# Control.net
KiCad netlist of a schematic drawn in Altium Designer
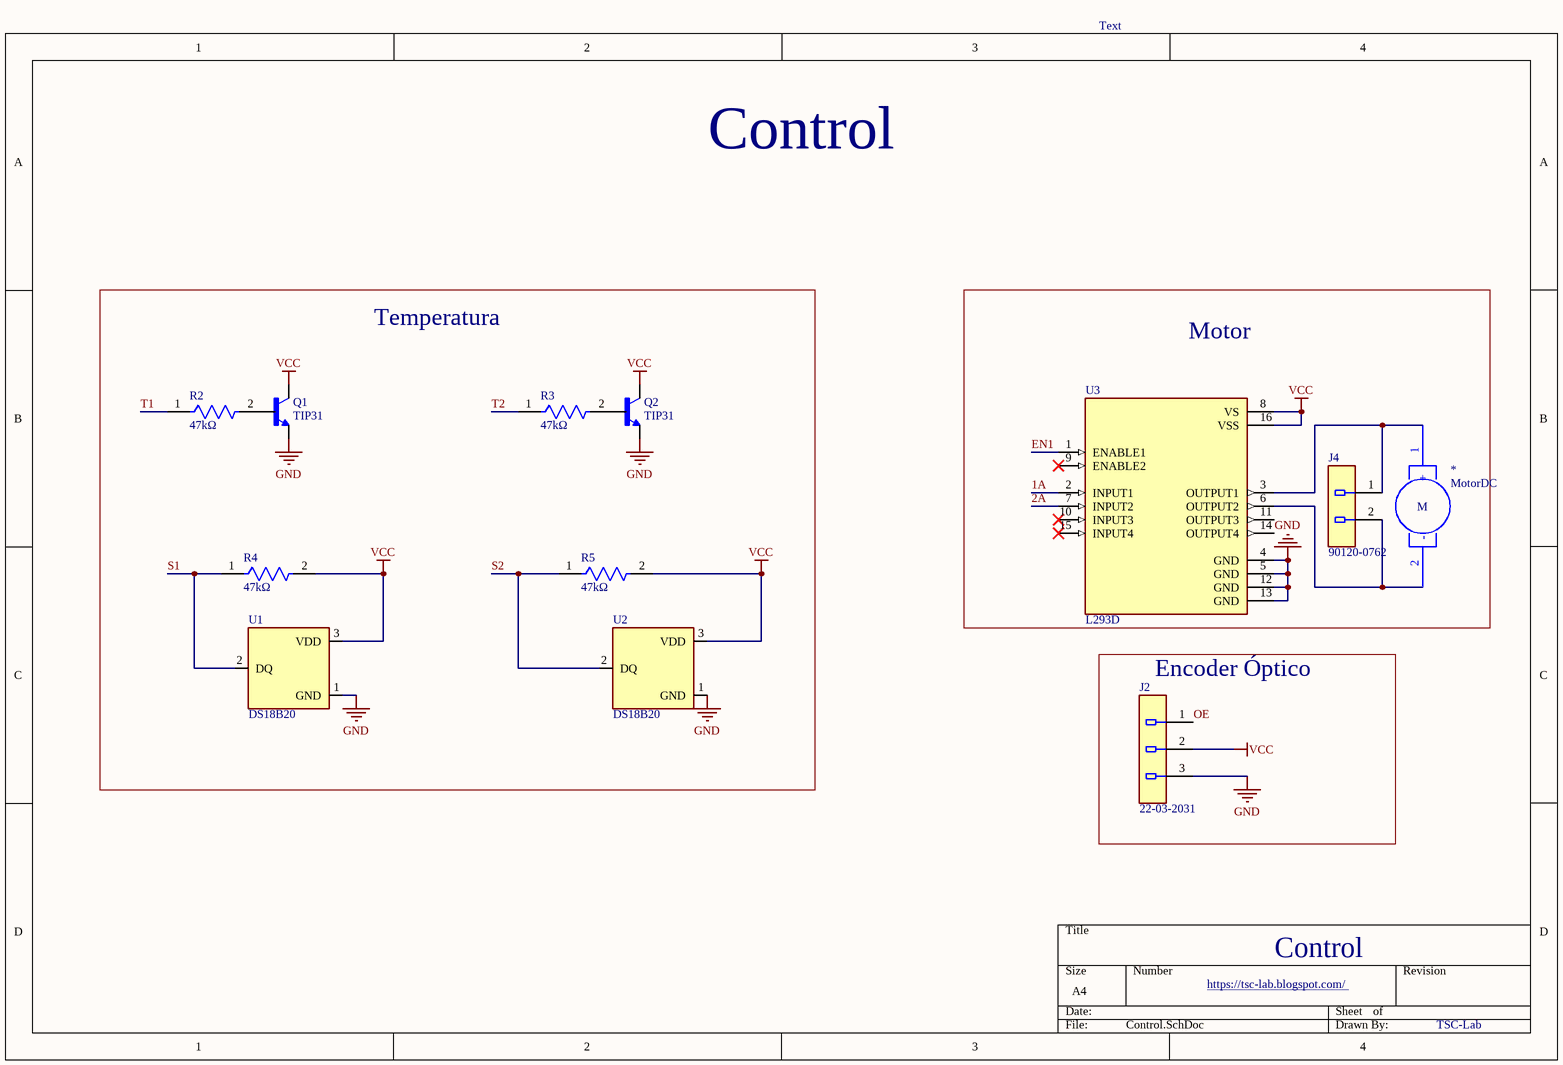
[diagram p0: Control.SchDoc]

(export (version "E")
  (design (tool "Eeschema 10.0.6"))
  (components
    (comp (ref "*")
      (value "MotorDC")
      (footprint "PCBComponent_1")
      (libsource (lib "SnapEDA_Library") (part "MotorDC"))
    )
    (comp (ref "J2")
      (value "Conn_Molex_22-03-2031_eec")
      (footprint "Molex_SD-4030-0001_0")
      (description "CONN HEADER 3POS .100 VERT TIN")
      (fields
        (field (name "PART NUMBER") "22-03-2031")
        (field (name "VOLTAGE") "150V")
        (field (name "MANUFACTURER") "Molex")
      )
      (libsource (lib "SnapEDA_Library") (part "Conn_Molex_22-03-2031_eec"))
    )
    (comp (ref "J4")
      (value "Conn_Molex_90120-0762_eec")
      (footprint "Molex_90120-0762_0")
      (description "CONN HEADER 2POS .100\" STR GOLD")
      (fields
        (field (name "MANUFACTURER") "Molex")
        (field (name "MOUSER PART NUMBER") "538-90120-0762")
        (field (name "PART NUMBER") "90120-0762")
      )
      (libsource (lib "SnapEDA_Library") (part "Conn_Molex_90120-0762_eec"))
    )
    (comp (ref "Q1")
      (value "TIP31")
      (footprint "TO254P1060X482X2222-3")
      (description "Bipolar (BJT) Transistor NPN 40V 3A 3MHz 2W Through Hole TO-220AB")
      (fields (field (name "MF") "{'manufacturer': u'ON Semiconductor'}"))
      (libsource (lib "SnapEDA_Library") (part "TIP31"))
    )
    (comp (ref "Q2")
      (value "TIP31")
      (footprint "TO254P1060X482X2222-3")
      (description "Bipolar (BJT) Transistor NPN 40V 3A 3MHz 2W Through Hole TO-220AB")
      (fields (field (name "MF") "{'manufacturer': u'ON Semiconductor'}"))
      (libsource (lib "SnapEDA_Library") (part "TIP31"))
    )
    (comp (ref "R2")
      (value "Res_Vishay_SFR2500002200FR500_eec")
      (footprint "Vishay_SFR2500002200FR500_0")
      (description "RES 220 OHM 0.4W 1% AXIAL")
      (fields
        (field (name "PART NUMBER") "SFR2500002200FR500")
        (field (name "VOLTAGE") "250 V")
        (field (name "RESISTANCE") "47kΩ")
      )
      (libsource (lib "SnapEDA_Library") (part "Res_Vishay_SFR2500002200FR500_eec"))
    )
    (comp (ref "R3")
      (value "Res_Vishay_SFR2500002200FR500_eec")
      (footprint "Vishay_SFR2500002200FR500_0")
      (description "RES 220 OHM 0.4W 1% AXIAL")
      (fields
        (field (name "PART NUMBER") "SFR2500002200FR500")
        (field (name "VOLTAGE") "250 V")
        (field (name "RESISTANCE") "47kΩ")
      )
      (libsource (lib "SnapEDA_Library") (part "Res_Vishay_SFR2500002200FR500_eec"))
    )
    (comp (ref "R4")
      (value "Res_Vishay_SFR2500002200FR500_eec")
      (footprint "Vishay_SFR2500002200FR500_0")
      (description "RES 220 OHM 0.4W 1% AXIAL")
      (fields
        (field (name "PART NUMBER") "SFR2500002200FR500")
        (field (name "VOLTAGE") "250 V")
        (field (name "RESISTANCE") "47kΩ")
      )
      (libsource (lib "SnapEDA_Library") (part "Res_Vishay_SFR2500002200FR500_eec"))
    )
    (comp (ref "R5")
      (value "Res_Vishay_SFR2500002200FR500_eec")
      (footprint "Vishay_SFR2500002200FR500_0")
      (description "RES 220 OHM 0.4W 1% AXIAL")
      (fields
        (field (name "PART NUMBER") "SFR2500002200FR500")
        (field (name "VOLTAGE") "250 V")
        (field (name "RESISTANCE") "47kΩ")
      )
      (libsource (lib "SnapEDA_Library") (part "Res_Vishay_SFR2500002200FR500_eec"))
    )
    (comp (ref "U1")
      (value "DS18B20")
      (footprint "TO-92-TO92127P495H2044-3")
      (description "digital thermometer -55C-125C TO92-3")
      (fields (field (name "MF") "{'manufacturer': u'Maxim Integrated'}"))
      (libsource (lib "SnapEDA_Library") (part "DS18B20"))
    )
    (comp (ref "U2")
      (value "DS18B20")
      (footprint "TO-92-TO92127P495H2044-3")
      (description "digital thermometer -55C-125C TO92-3")
      (fields (field (name "MF") "{'manufacturer': u'Maxim Integrated'}"))
      (libsource (lib "SnapEDA_Library") (part "DS18B20"))
    )
    (comp (ref "U3")
      (value "L293D")
      (footprint "DIP880W50P254L2000H510Q16")
      (description "4-Channel Motor Driver 24V 16-Pin Power PDIP Tube")
      (fields (field (name "MF") "{'manufacturer': u'STMicroelectronics'}"))
      (libsource (lib "SnapEDA_Library") (part "L293D"))
    )
  )
  (nets
    (net (code "1") (name "/1A") (class "Default")
      (node (ref "U3") (pin "2") (pinfunction "INPUT1_2") (pintype "input"))
    )
    (net (code "2") (name "/2A") (class "Default")
      (node (ref "U3") (pin "7") (pinfunction "INPUT2_7") (pintype "input"))
    )
    (net (code "3") (name "/EN1") (class "Default")
      (node (ref "U3") (pin "1") (pinfunction "ENABLE1_1") (pintype "input"))
    )
    (net (code "4") (name "/OE") (class "Default")
      (node (ref "J2") (pin "1") (pinfunction "1_1") (pintype "passive"))
    )
    (net (code "5") (name "/S1") (class "Default")
      (node (ref "R4") (pin "1") (pinfunction "1_1") (pintype "passive"))
      (node (ref "U1") (pin "2") (pinfunction "DQ_2") (pintype "bidirectional"))
    )
    (net (code "6") (name "/S2") (class "Default")
      (node (ref "R5") (pin "1") (pinfunction "1_1") (pintype "passive"))
      (node (ref "U2") (pin "2") (pinfunction "DQ_2") (pintype "bidirectional"))
    )
    (net (code "7") (name "/T1") (class "Default")
      (node (ref "R2") (pin "1") (pinfunction "1_1") (pintype "passive"))
    )
    (net (code "8") (name "/T2") (class "Default")
      (node (ref "R3") (pin "1") (pinfunction "1_1") (pintype "passive"))
    )
    (net (code "9") (name "GND") (class "Default")
      (node (ref "J2") (pin "3") (pinfunction "3_3") (pintype "passive"))
      (node (ref "Q1") (pin "3") (pinfunction "E_3") (pintype "passive"))
      (node (ref "Q2") (pin "3") (pinfunction "E_3") (pintype "passive"))
      (node (ref "U1") (pin "1") (pinfunction "GND_1") (pintype "power_in"))
      (node (ref "U2") (pin "1") (pinfunction "GND_1") (pintype "power_in"))
      (node (ref "U3") (pin "12") (pinfunction "GND_12") (pintype "power_in"))
      (node (ref "U3") (pin "13") (pinfunction "GND_13") (pintype "power_in"))
      (node (ref "U3") (pin "4") (pinfunction "GND_4") (pintype "power_in"))
      (node (ref "U3") (pin "5") (pinfunction "GND_5") (pintype "power_in"))
    )
    (net (code "10") (name "Net-(*-+)") (class "Default")
      (node (ref "*") (pin "1") (pinfunction "+_1") (pintype "passive"))
      (node (ref "J4") (pin "1") (pinfunction "1_1") (pintype "passive"))
      (node (ref "U3") (pin "3") (pinfunction "OUTPUT1_3") (pintype "output"))
    )
    (net (code "11") (name "Net-(*--)") (class "Default")
      (node (ref "*") (pin "2") (pinfunction "-_2") (pintype "passive"))
      (node (ref "J4") (pin "2") (pinfunction "2_2") (pintype "passive"))
      (node (ref "U3") (pin "6") (pinfunction "OUTPUT2_6") (pintype "output"))
    )
    (net (code "12") (name "Net-(Q1-B)") (class "Default")
      (node (ref "Q1") (pin "1") (pinfunction "B_1") (pintype "passive"))
      (node (ref "R2") (pin "2") (pinfunction "2_2") (pintype "passive"))
    )
    (net (code "13") (name "Net-(Q2-B)") (class "Default")
      (node (ref "Q2") (pin "1") (pinfunction "B_1") (pintype "passive"))
      (node (ref "R3") (pin "2") (pinfunction "2_2") (pintype "passive"))
    )
    (net (code "14") (name "VCC") (class "Default")
      (node (ref "J2") (pin "2") (pinfunction "2_2") (pintype "passive"))
      (node (ref "Q1") (pin "2") (pinfunction "C_2") (pintype "passive"))
      (node (ref "Q2") (pin "2") (pinfunction "C_2") (pintype "passive"))
      (node (ref "R4") (pin "2") (pinfunction "2_2") (pintype "passive"))
      (node (ref "R5") (pin "2") (pinfunction "2_2") (pintype "passive"))
      (node (ref "U1") (pin "3") (pinfunction "VDD_3") (pintype "power_in"))
      (node (ref "U2") (pin "3") (pinfunction "VDD_3") (pintype "power_in"))
      (node (ref "U3") (pin "16") (pinfunction "VSS_16") (pintype "power_in"))
      (node (ref "U3") (pin "8") (pinfunction "VS_8") (pintype "power_in"))
    )
    (net (code "15") (name "unconnected-(U3-ENABLE2-Pad9)") (class "Default")
      (node (ref "U3") (pin "9") (pinfunction "ENABLE2_9") (pintype "input+no_connect"))
    )
    (net (code "16") (name "unconnected-(U3-INPUT3-Pad10)") (class "Default")
      (node (ref "U3") (pin "10") (pinfunction "INPUT3_10") (pintype "input+no_connect"))
    )
    (net (code "17") (name "unconnected-(U3-INPUT4-Pad15)") (class "Default")
      (node (ref "U3") (pin "15") (pinfunction "INPUT4_15") (pintype "input+no_connect"))
    )
    (net (code "18") (name "unconnected-(U3-OUTPUT3-Pad11)") (class "Default")
      (node (ref "U3") (pin "11") (pinfunction "OUTPUT3_11") (pintype "output"))
    )
    (net (code "19") (name "unconnected-(U3-OUTPUT4-Pad14)") (class "Default")
      (node (ref "U3") (pin "14") (pinfunction "OUTPUT4_14") (pintype "output"))
    )
  )
)
